# RS-232.net
KiCad netlist of a schematic drawn in Altium Designer
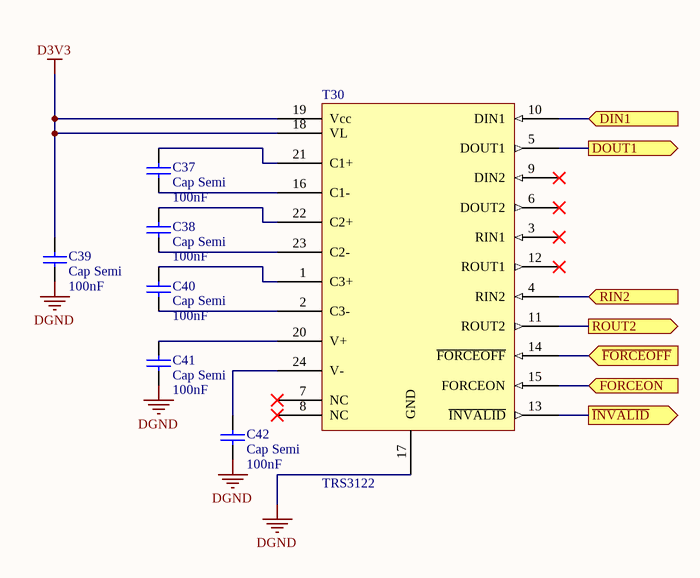
[diagram p0: RS-232.SchDoc]

(export (version "E")
  (design (tool "Eeschema 10.0.6"))
  (components
    (comp (ref "C37")
      (value "Cap Semi")
      (footprint "1608[0603]")
      (description "Capacitor (Semiconductor SIM Model)")
      (fields (field (name "ALTIUM_VALUE") "100nF") (field (name "PUBLISHER") "Altium Limited"))
      (libsource (lib "Miscellaneous Devices") (part "Cap Semi"))
    )
    (comp (ref "C38")
      (value "Cap Semi")
      (footprint "1608[0603]")
      (description "Capacitor (Semiconductor SIM Model)")
      (fields (field (name "ALTIUM_VALUE") "100nF") (field (name "PUBLISHER") "Altium Limited"))
      (libsource (lib "Miscellaneous Devices") (part "Cap Semi"))
    )
    (comp (ref "C39")
      (value "Cap Semi")
      (footprint "1608[0603]")
      (description "Capacitor (Semiconductor SIM Model)")
      (fields (field (name "ALTIUM_VALUE") "100nF") (field (name "PUBLISHER") "Altium Limited"))
      (libsource (lib "Miscellaneous Devices") (part "Cap Semi"))
    )
    (comp (ref "C40")
      (value "Cap Semi")
      (footprint "1608[0603]")
      (description "Capacitor (Semiconductor SIM Model)")
      (fields (field (name "ALTIUM_VALUE") "100nF") (field (name "PUBLISHER") "Altium Limited"))
      (libsource (lib "Miscellaneous Devices") (part "Cap Semi"))
    )
    (comp (ref "C41")
      (value "Cap Semi")
      (footprint "1608[0603]")
      (description "Capacitor (Semiconductor SIM Model)")
      (fields (field (name "ALTIUM_VALUE") "100nF") (field (name "PUBLISHER") "Altium Limited"))
      (libsource (lib "Miscellaneous Devices") (part "Cap Semi"))
    )
    (comp (ref "C42")
      (value "Cap Semi")
      (footprint "1608[0603]")
      (description "Capacitor (Semiconductor SIM Model)")
      (fields (field (name "ALTIUM_VALUE") "100nF") (field (name "PUBLISHER") "Altium Limited"))
      (libsource (lib "Miscellaneous Devices") (part "Cap Semi"))
    )
    (comp (ref "T30")
      (value "TRS3122")
      (footprint "QFN50P485X485X100_HS-25N")
      (libsource (lib "TRS3122") (part "Component_1"))
    )
  )
  (nets
    (net (code "1") (name "/DIN1") (class "Default")
      (node (ref "T30") (pin "10") (pinfunction "DIN1_10") (pintype "input"))
    )
    (net (code "2") (name "/DOUT1") (class "Default")
      (node (ref "T30") (pin "5") (pinfunction "DOUT1_5") (pintype "output"))
    )
    (net (code "3") (name "/FORCEON") (class "Default")
      (node (ref "T30") (pin "15") (pinfunction "FORCEON_15") (pintype "input"))
    )
    (net (code "4") (name "/RIN2") (class "Default")
      (node (ref "T30") (pin "4") (pinfunction "RIN2_4") (pintype "input"))
    )
    (net (code "5") (name "/ROUT2") (class "Default")
      (node (ref "T30") (pin "11") (pinfunction "ROUT2_11") (pintype "output"))
    )
    (net (code "6") (name "/~{FORCEOFF}") (class "Default")
      (node (ref "T30") (pin "14") (pinfunction "~{FORCEOFF}_14") (pintype "input"))
    )
    (net (code "7") (name "/~{INVALID}") (class "Default")
      (node (ref "T30") (pin "13") (pinfunction "~{INVALID}_13") (pintype "output"))
    )
    (net (code "8") (name "D3V3") (class "Default")
      (node (ref "C39") (pin "1") (pinfunction "1_1") (pintype "passive"))
      (node (ref "T30") (pin "18") (pinfunction "VL_18") (pintype "passive"))
      (node (ref "T30") (pin "19") (pinfunction "Vcc_19") (pintype "passive"))
    )
    (net (code "9") (name "DGND") (class "Default")
      (node (ref "C39") (pin "2") (pinfunction "2_2") (pintype "passive"))
      (node (ref "C41") (pin "2") (pinfunction "2_2") (pintype "passive"))
      (node (ref "C42") (pin "2") (pinfunction "2_2") (pintype "passive"))
      (node (ref "T30") (pin "17") (pinfunction "GND_17") (pintype "passive"))
    )
    (net (code "10") (name "Net-(T30-C1+)") (class "Default")
      (node (ref "C37") (pin "1") (pinfunction "1_1") (pintype "passive"))
      (node (ref "T30") (pin "21") (pinfunction "C1+_21") (pintype "passive"))
    )
    (net (code "11") (name "Net-(T30-C1-)") (class "Default")
      (node (ref "C37") (pin "2") (pinfunction "2_2") (pintype "passive"))
      (node (ref "T30") (pin "16") (pinfunction "C1-_16") (pintype "passive"))
    )
    (net (code "12") (name "Net-(T30-C2+)") (class "Default")
      (node (ref "C38") (pin "1") (pinfunction "1_1") (pintype "passive"))
      (node (ref "T30") (pin "22") (pinfunction "C2+_22") (pintype "passive"))
    )
    (net (code "13") (name "Net-(T30-C2-)") (class "Default")
      (node (ref "C38") (pin "2") (pinfunction "2_2") (pintype "passive"))
      (node (ref "T30") (pin "23") (pinfunction "C2-_23") (pintype "passive"))
    )
    (net (code "14") (name "Net-(T30-C3+)") (class "Default")
      (node (ref "C40") (pin "1") (pinfunction "1_1") (pintype "passive"))
      (node (ref "T30") (pin "1") (pinfunction "C3+_1") (pintype "passive"))
    )
    (net (code "15") (name "Net-(T30-C3-)") (class "Default")
      (node (ref "C40") (pin "2") (pinfunction "2_2") (pintype "passive"))
      (node (ref "T30") (pin "2") (pinfunction "C3-_2") (pintype "passive"))
    )
    (net (code "16") (name "Net-(T30-V+)") (class "Default")
      (node (ref "C41") (pin "1") (pinfunction "1_1") (pintype "passive"))
      (node (ref "T30") (pin "20") (pinfunction "V+_20") (pintype "passive"))
    )
    (net (code "17") (name "Net-(T30-V-)") (class "Default")
      (node (ref "C42") (pin "1") (pinfunction "1_1") (pintype "passive"))
      (node (ref "T30") (pin "24") (pinfunction "V-_24") (pintype "passive"))
    )
    (net (code "18") (name "unconnected-(T30-DIN2-Pad9)") (class "Default")
      (node (ref "T30") (pin "9") (pinfunction "DIN2_9") (pintype "input+no_connect"))
    )
    (net (code "19") (name "unconnected-(T30-DOUT2-Pad6)") (class "Default")
      (node (ref "T30") (pin "6") (pinfunction "DOUT2_6") (pintype "output+no_connect"))
    )
    (net (code "20") (name "unconnected-(T30-NC-Pad7)") (class "Default")
      (node (ref "T30") (pin "7") (pinfunction "NC_7") (pintype "passive+no_connect"))
    )
    (net (code "21") (name "unconnected-(T30-NC-Pad8)") (class "Default")
      (node (ref "T30") (pin "8") (pinfunction "NC_8") (pintype "passive+no_connect"))
    )
    (net (code "22") (name "unconnected-(T30-RIN1-Pad3)") (class "Default")
      (node (ref "T30") (pin "3") (pinfunction "RIN1_3") (pintype "input+no_connect"))
    )
    (net (code "23") (name "unconnected-(T30-ROUT1-Pad12)") (class "Default")
      (node (ref "T30") (pin "12") (pinfunction "ROUT1_12") (pintype "output+no_connect"))
    )
  )
)
